# TP_IHM_BUZZER.net
KiCad netlist of a schematic drawn in Altium Designer
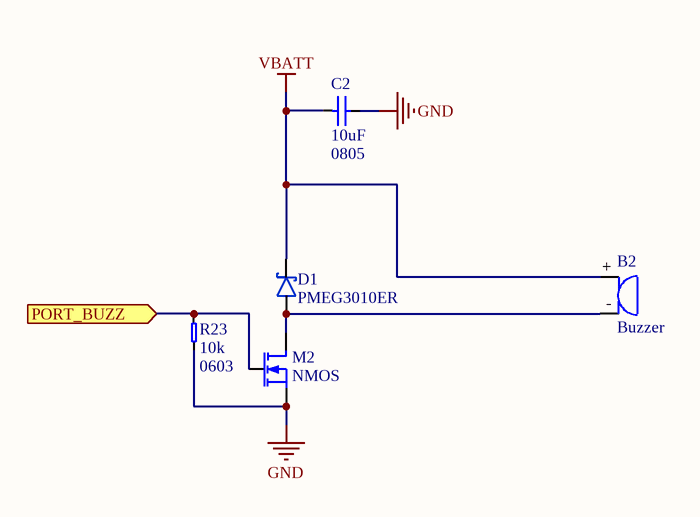
[diagram p0: TP_IHM_BUZZER.SchDoc]

(export (version "E")
  (design (tool "Eeschema 10.0.6"))
  (components
    (comp (ref "B2")
      (value "Buzzer")
      (footprint "SD160709")
      (description "TDK SD160709 Buzzer")
      (libsource (lib "TpGiven") (part "SD160709"))
    )
    (comp (ref "C2")
      (value "10uF")
      (footprint "0805_CAP_LD")
      (description "Ceramic Capacitor")
      (fields (field (name "PACKAGE") "0805") (field (name "Comment") "CerCap"))
      (libsource (lib "TpGiven") (part "CerCap"))
    )
    (comp (ref "D1")
      (value "PMEG3010ER")
      (footprint "SOD123W")
      (description "Nexperia 1A low Vf Mega Schottky barrier rectifier")
      (libsource (lib "TpGiven") (part "Schottky_PMEG3010ER"))
    )
    (comp (ref "M2")
      (value "NMOS")
      (footprint "MOSFET-SOT23")
      (description "N MOSFET")
      (libsource (lib "TpGiven") (part "N-MOSFET"))
    )
    (comp (ref "R23")
      (value "10k")
      (footprint "0603_RES_LD")
      (description "Resistor")
      (fields (field (name "PACKAGE") "0603"))
      (libsource (lib "TpGiven") (part "Resistor"))
    )
  )
  (nets
    (net (code "1") (name "/PORT_BUZZ") (class "Default")
      (node (ref "M2") (pin "G") (pinfunction "G_G") (pintype "passive"))
      (node (ref "R23") (pin "2") (pinfunction "2_2") (pintype "passive"))
    )
    (net (code "2") (name "GND") (class "Default")
      (node (ref "C2") (pin "2") (pinfunction "2_2") (pintype "passive"))
      (node (ref "M2") (pin "S") (pinfunction "S_S") (pintype "passive"))
      (node (ref "R23") (pin "1") (pinfunction "1_1") (pintype "passive"))
    )
    (net (code "3") (name "Net-(D1-1)") (class "Default")
      (node (ref "B2") (pin "-") (pinfunction "-_-") (pintype "passive"))
      (node (ref "D1") (pin "A") (pinfunction "1_A") (pintype "passive"))
      (node (ref "M2") (pin "D") (pinfunction "D_D") (pintype "passive"))
    )
    (net (code "4") (name "VBATT") (class "Default")
      (node (ref "B2") (pin "+") (pinfunction "+_+") (pintype "passive"))
      (node (ref "C2") (pin "1") (pinfunction "1_1") (pintype "passive"))
      (node (ref "D1") (pin "K") (pinfunction "2_K") (pintype "passive"))
    )
  )
)
